# XIAO_ESP32S3_v1_1.net
KiCad netlist of a schematic drawn in EAGLE
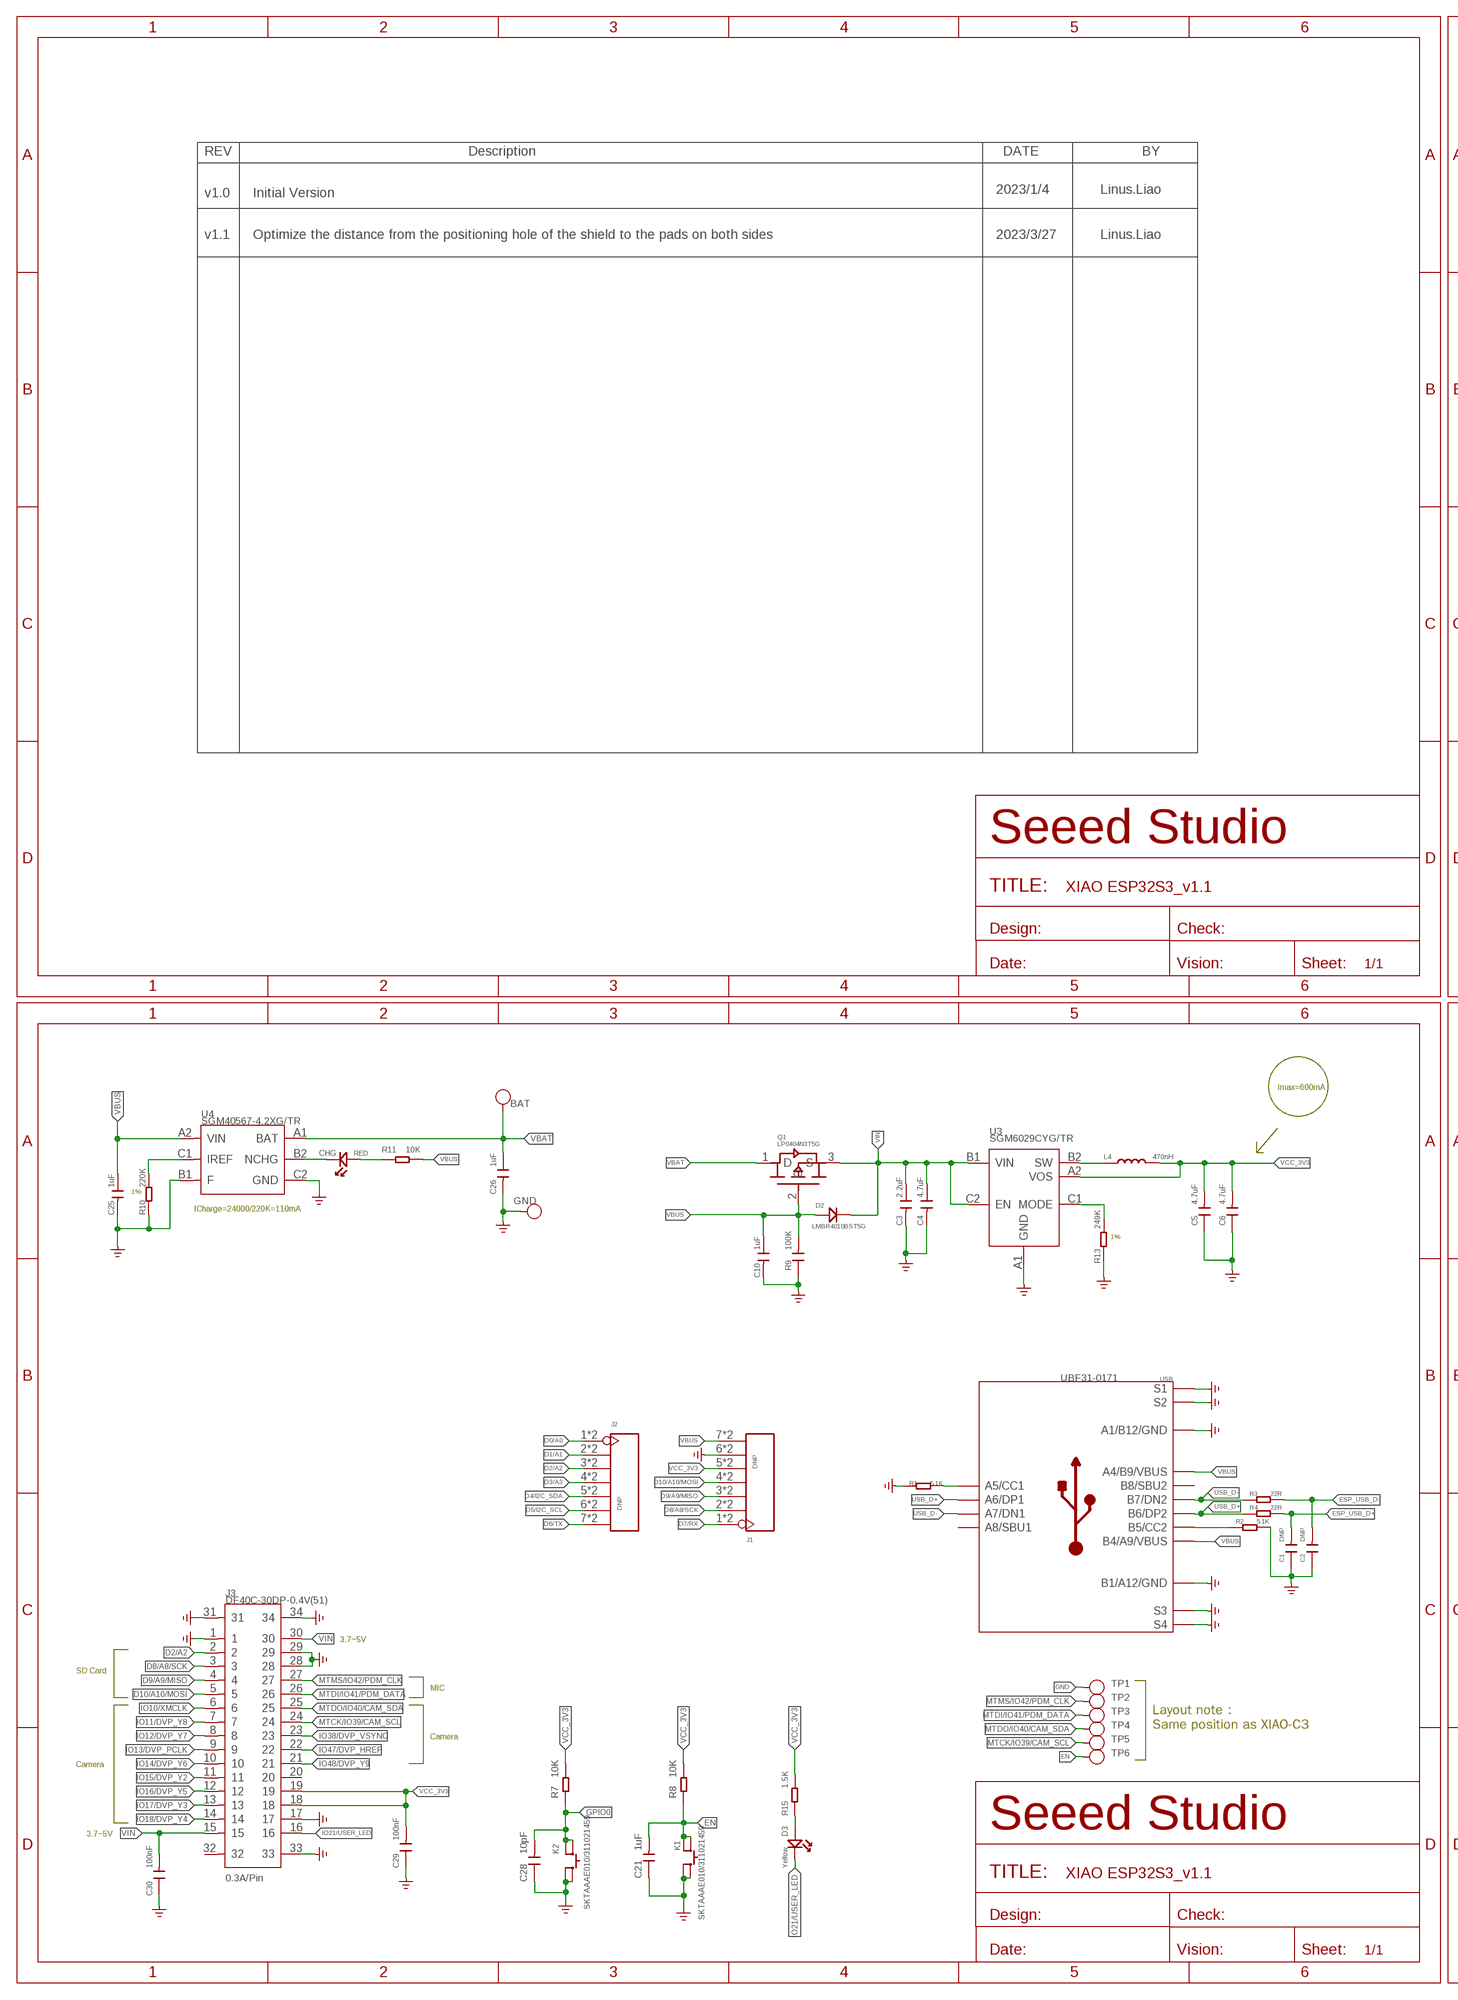
[diagram p0: schematic, sheet 1, part 1 of 2]
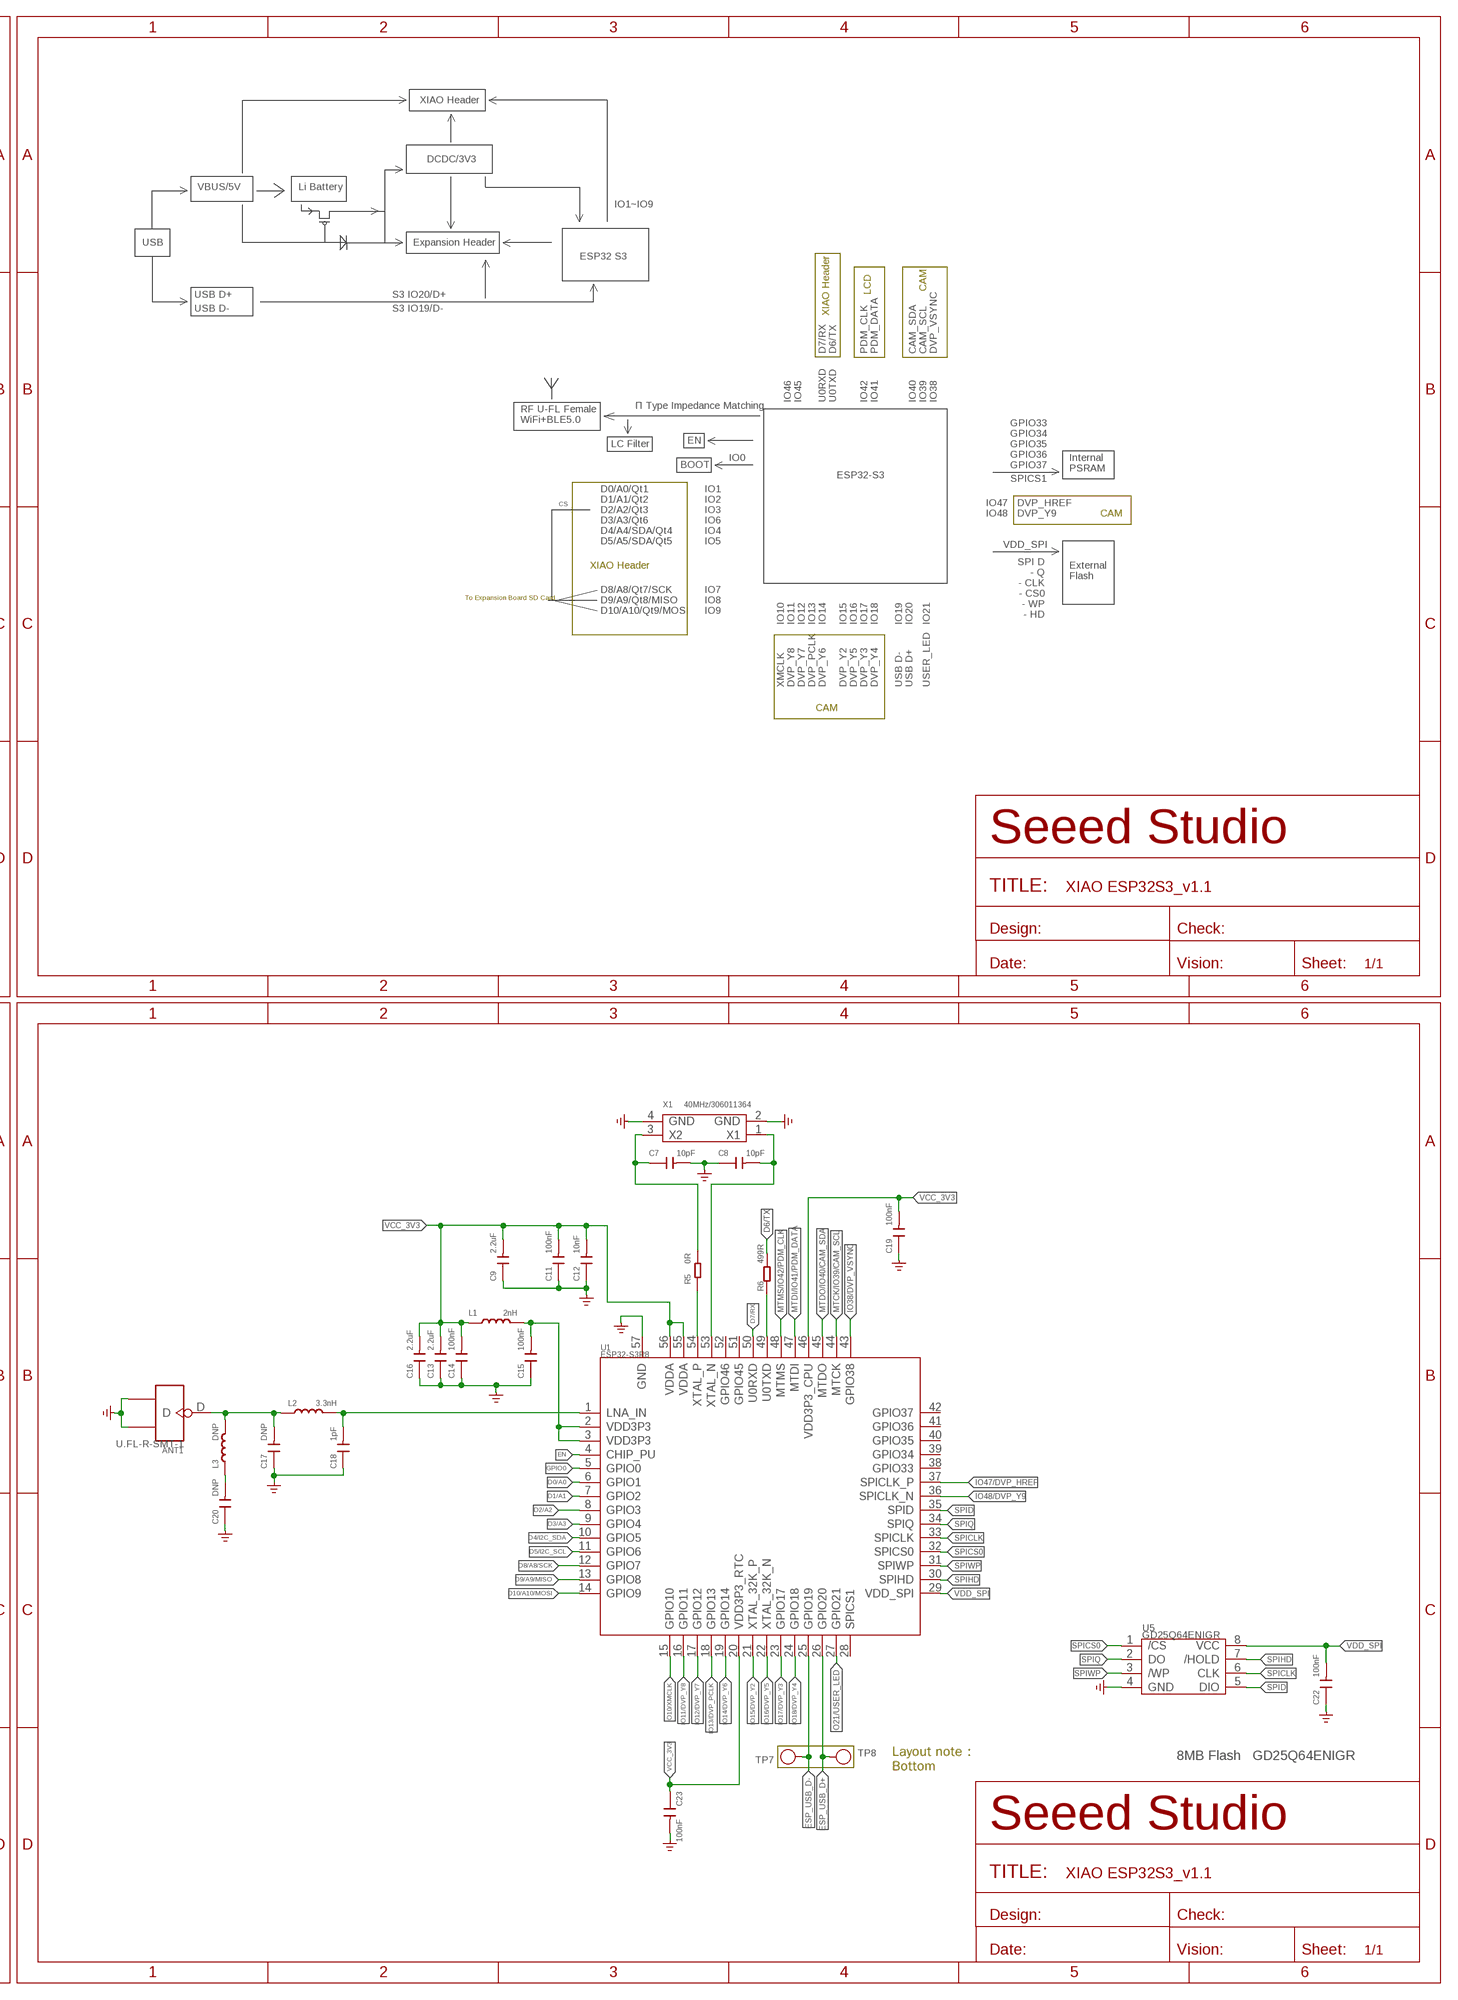
[diagram p1: schematic, sheet 1, part 2 of 2]

(export (version "E")
  (design (tool "Eeschema 10.0.6"))
  (components
    (comp (ref "ANT1")
      (value "U.FL-R-SMT-1")
      (footprint "eagle-import:U-FL3P-SMD-2.6X2.6X1.0MM")
      (libsource (lib "eagle-import") (part "ANTENNA-U-FL-320110048"))
    )
    (comp (ref "BAT")
      (value "VBAT")
      (footprint "eagle-import:TP-80X40MIL")
      (libsource (lib "eagle-import") (part "TEST-POINT'4080'"))
    )
    (comp (ref "C1")
      (value "DNP")
      (footprint "eagle-import:C0201")
      (libsource (lib "eagle-import") (part "CAP-0201"))
    )
    (comp (ref "C2")
      (value "DNP")
      (footprint "eagle-import:C0201")
      (libsource (lib "eagle-import") (part "CAP-0201"))
    )
    (comp (ref "C3")
      (value "2.2uF")
      (footprint "eagle-import:C0201")
      (libsource (lib "eagle-import") (part "CAP-0201"))
    )
    (comp (ref "C4")
      (value "4.7uF")
      (footprint "eagle-import:C0201")
      (libsource (lib "eagle-import") (part "CAP-0201"))
    )
    (comp (ref "C5")
      (value "4.7uF")
      (footprint "eagle-import:C0201")
      (libsource (lib "eagle-import") (part "CAP-0201"))
    )
    (comp (ref "C6")
      (value "4.7uF")
      (footprint "eagle-import:C0201")
      (libsource (lib "eagle-import") (part "CAP-0201"))
    )
    (comp (ref "C7")
      (value "10pF")
      (footprint "eagle-import:C0201")
      (libsource (lib "eagle-import") (part "CAP-0201"))
    )
    (comp (ref "C8")
      (value "10pF")
      (footprint "eagle-import:C0201")
      (libsource (lib "eagle-import") (part "CAP-0201"))
    )
    (comp (ref "C9")
      (value "2.2uF")
      (footprint "eagle-import:C0201")
      (libsource (lib "eagle-import") (part "CAP-0201"))
    )
    (comp (ref "C10")
      (value "1uF")
      (footprint "eagle-import:C0201")
      (libsource (lib "eagle-import") (part "CAP-0201"))
    )
    (comp (ref "C11")
      (value "100nF")
      (footprint "eagle-import:C0201")
      (libsource (lib "eagle-import") (part "CAP-0201"))
    )
    (comp (ref "C12")
      (value "10nF")
      (footprint "eagle-import:C0201")
      (libsource (lib "eagle-import") (part "CAP-0201"))
    )
    (comp (ref "C13")
      (value "2.2uF")
      (footprint "eagle-import:C0201")
      (libsource (lib "eagle-import") (part "CAP-0201"))
    )
    (comp (ref "C14")
      (value "100nF")
      (footprint "eagle-import:C0201")
      (libsource (lib "eagle-import") (part "CAP-0201"))
    )
    (comp (ref "C15")
      (value "100nF")
      (footprint "eagle-import:C0201")
      (libsource (lib "eagle-import") (part "CAP-0201"))
    )
    (comp (ref "C16")
      (value "2.2uF")
      (footprint "eagle-import:C0201")
      (libsource (lib "eagle-import") (part "CAP-0201"))
    )
    (comp (ref "C17")
      (value "DNP")
      (footprint "eagle-import:C0201")
      (libsource (lib "eagle-import") (part "CAP-0201"))
    )
    (comp (ref "C18")
      (value "1pF")
      (footprint "eagle-import:C0201")
      (libsource (lib "eagle-import") (part "CAP-0201"))
    )
    (comp (ref "C19")
      (value "100nF")
      (footprint "eagle-import:C0201")
      (libsource (lib "eagle-import") (part "CAP-0201"))
    )
    (comp (ref "C20")
      (value "DNP")
      (footprint "eagle-import:C0201")
      (libsource (lib "eagle-import") (part "CAP-0201"))
    )
    (comp (ref "C21")
      (value "1uF")
      (footprint "eagle-import:C0201")
      (libsource (lib "eagle-import") (part "CAP-0201"))
    )
    (comp (ref "C22")
      (value "100nF")
      (footprint "eagle-import:C0201")
      (libsource (lib "eagle-import") (part "CAP-0201"))
    )
    (comp (ref "C23")
      (value "100nF")
      (footprint "eagle-import:C0201")
      (libsource (lib "eagle-import") (part "CAP-0201"))
    )
    (comp (ref "C25")
      (value "1uF")
      (footprint "eagle-import:C0201")
      (libsource (lib "eagle-import") (part "CAP-0201"))
    )
    (comp (ref "C26")
      (value "1uF")
      (footprint "eagle-import:C0201")
      (libsource (lib "eagle-import") (part "CAP-0201"))
    )
    (comp (ref "C28")
      (value "10pF")
      (footprint "eagle-import:C0201")
      (libsource (lib "eagle-import") (part "CAP-0201"))
    )
    (comp (ref "C29")
      (value "100nF")
      (footprint "eagle-import:C0201")
      (libsource (lib "eagle-import") (part "CAP-0201"))
    )
    (comp (ref "C30")
      (value "100nF")
      (footprint "eagle-import:C0201")
      (libsource (lib "eagle-import") (part "CAP-0201"))
    )
    (comp (ref "CHG")
      (value "RED")
      (footprint "eagle-import:LED-0402")
      (libsource (lib "eagle-import") (part "LED-0402"))
    )
    (comp (ref "D2")
      (value "LMBR4010BST5G")
      (footprint "eagle-import:DFN1006-2L")
      (libsource (lib "eagle-import") (part "DIODEDFN1006(0402/SOD882)"))
    )
    (comp (ref "D3")
      (value "Yellow")
      (footprint "eagle-import:LED-0402")
      (libsource (lib "eagle-import") (part "LED-0402"))
    )
    (comp (ref "GND")
      (value "GND")
      (footprint "eagle-import:TP-80X40MIL")
      (libsource (lib "eagle-import") (part "TEST-POINT'4080'"))
    )
    (comp (ref "J1")
      (value "DNP")
      (footprint "eagle-import:H7-HALF-HOLE-2.54")
      (libsource (lib "eagle-import") (part "HEADER-7P-HALF-HOLE-2.54"))
    )
    (comp (ref "J2")
      (value "DNP")
      (footprint "eagle-import:H7-HALF-HOLE-2.54")
      (libsource (lib "eagle-import") (part "HEADER-7P-HALF-HOLE-2.54"))
    )
    (comp (ref "J3")
      (value "DF40C-30DP-0.4V(51)")
      (footprint "eagle-import:BTB30-0.4-7.52X2.97X1.14")
      (libsource (lib "eagle-import") (part "BTB-P4S30-HEAD"))
    )
    (comp (ref "K1")
      (value "SKTAAAE010/311021459")
      (footprint "eagle-import:SW4-SMD-2.8-2.6X1.6X0.53MM")
      (libsource (lib "eagle-import") (part "BUTTON-4P"))
    )
    (comp (ref "K2")
      (value "SKTAAAE010/311021459")
      (footprint "eagle-import:SW4-SMD-2.8-2.6X1.6X0.53MM")
      (libsource (lib "eagle-import") (part "BUTTON-4P"))
    )
    (comp (ref "L1")
      (value "2nH")
      (footprint "eagle-import:L0201")
      (libsource (lib "eagle-import") (part "INDUCTOR-0201"))
    )
    (comp (ref "L2")
      (value "3.3nH")
      (footprint "eagle-import:L0201")
      (libsource (lib "eagle-import") (part "INDUCTOR-0201"))
    )
    (comp (ref "L3")
      (value "DNP")
      (footprint "eagle-import:L0201")
      (libsource (lib "eagle-import") (part "INDUCTOR-0201"))
    )
    (comp (ref "L4")
      (value "470nH")
      (footprint "eagle-import:L0603")
      (libsource (lib "eagle-import") (part "L-0603"))
    )
    (comp (ref "Q1")
      (value "LP0404N3T5G")
      (footprint "eagle-import:PMOS_1.0_0.6_0.35MM")
      (libsource (lib "eagle-import") (part "PMOS_1.00.60.35MM"))
    )
    (comp (ref "R1")
      (value "5.1K")
      (footprint "eagle-import:R0201")
      (libsource (lib "eagle-import") (part "RES-0201"))
    )
    (comp (ref "R2")
      (value "5.1K")
      (footprint "eagle-import:R0201")
      (libsource (lib "eagle-import") (part "RES-0201"))
    )
    (comp (ref "R3")
      (value "22R")
      (footprint "eagle-import:R0201")
      (libsource (lib "eagle-import") (part "RES-0201"))
    )
    (comp (ref "R4")
      (value "22R")
      (footprint "eagle-import:R0201")
      (libsource (lib "eagle-import") (part "RES-0201"))
    )
    (comp (ref "R5")
      (value "0R")
      (footprint "eagle-import:R0201")
      (libsource (lib "eagle-import") (part "RES-0201"))
    )
    (comp (ref "R6")
      (value "499R")
      (footprint "eagle-import:R0201")
      (libsource (lib "eagle-import") (part "RES-0201"))
    )
    (comp (ref "R7")
      (value "10K")
      (footprint "eagle-import:R0201")
      (libsource (lib "eagle-import") (part "RES-0201"))
    )
    (comp (ref "R8")
      (value "10K")
      (footprint "eagle-import:R0201")
      (libsource (lib "eagle-import") (part "RES-0201"))
    )
    (comp (ref "R9")
      (value "100K")
      (footprint "eagle-import:C0201")
      (libsource (lib "eagle-import") (part "CAP-0201"))
    )
    (comp (ref "R10")
      (value "220K")
      (footprint "eagle-import:R0201")
      (libsource (lib "eagle-import") (part "RES-0201"))
    )
    (comp (ref "R11")
      (value "10K")
      (footprint "eagle-import:R0201")
      (libsource (lib "eagle-import") (part "RES-0201"))
    )
    (comp (ref "R13")
      (value "249K")
      (footprint "eagle-import:R0201")
      (libsource (lib "eagle-import") (part "RES-0201"))
    )
    (comp (ref "R15")
      (value "1.5K")
      (footprint "eagle-import:R0201")
      (libsource (lib "eagle-import") (part "RES-0201"))
    )
    (comp (ref "TP1")
      (value "TEST-POINT'4545'")
      (footprint "eagle-import:TP-D45MIL")
      (fields (field (name "PARTNO") "DNP"))
      (libsource (lib "eagle-import") (part "TEST-POINT'4545'"))
    )
    (comp (ref "TP2")
      (value "TEST-POINT'4545'")
      (footprint "eagle-import:TP-D45MIL")
      (fields (field (name "PARTNO") "DNP"))
      (libsource (lib "eagle-import") (part "TEST-POINT'4545'"))
    )
    (comp (ref "TP3")
      (value "TEST-POINT'4545'")
      (footprint "eagle-import:TP-D45MIL")
      (fields (field (name "PARTNO") "DNP"))
      (libsource (lib "eagle-import") (part "TEST-POINT'4545'"))
    )
    (comp (ref "TP4")
      (value "TEST-POINT'4545'")
      (footprint "eagle-import:TP-D45MIL")
      (fields (field (name "PARTNO") "DNP"))
      (libsource (lib "eagle-import") (part "TEST-POINT'4545'"))
    )
    (comp (ref "TP5")
      (value "TEST-POINT'4545'")
      (footprint "eagle-import:TP-D45MIL")
      (fields (field (name "PARTNO") "DNP"))
      (libsource (lib "eagle-import") (part "TEST-POINT'4545'"))
    )
    (comp (ref "TP6")
      (value "TEST-POINT'4545'")
      (footprint "eagle-import:TP-D45MIL")
      (fields (field (name "PARTNO") "DNP"))
      (libsource (lib "eagle-import") (part "TEST-POINT'4545'"))
    )
    (comp (ref "TP7")
      (value "TEST-POINT'4545'")
      (footprint "eagle-import:TP-D45MIL")
      (fields (field (name "PARTNO") "DNP"))
      (libsource (lib "eagle-import") (part "TEST-POINT'4545'"))
    )
    (comp (ref "TP8")
      (value "TEST-POINT'4545'")
      (footprint "eagle-import:TP-D45MIL")
      (fields (field (name "PARTNO") "DNP"))
      (libsource (lib "eagle-import") (part "TEST-POINT'4545'"))
    )
    (comp (ref "U1")
      (value "ESP32-S3R8")
      (footprint "eagle-import:QFN56G-0.4-7X7MM")
      (libsource (lib "eagle-import") (part "MCU-ESP32-S3"))
    )
    (comp (ref "U3")
      (value "SGM6029CYG/TR")
      (footprint "eagle-import:BGA6-0.35-0.745X10.95X0.4MM")
      (libsource (lib "eagle-import") (part "PMIC-SGM6029"))
    )
    (comp (ref "U4")
      (value "SGM40567-4.2XG/TR")
      (footprint "eagle-import:WLCSP-0.4-0.92X1.16X0.4MM")
      (libsource (lib "eagle-import") (part "PMIC-SGM40567"))
    )
    (comp (ref "U5")
      (value "GD25Q64ENIGR")
      (footprint "eagle-import:USON8-0.8-4X3MM")
      (libsource (lib "eagle-import") (part "FLASH-W25X80-FZBIHO"))
    )
    (comp (ref "USB")
      (value "UBF31-0171")
      (footprint "eagle-import:USB2.0-TYPE-C")
      (libsource (lib "eagle-import") (part "USB2.0-TYPE-C"))
    )
    (comp (ref "X1")
      (value "40MHz/306011364")
      (footprint "eagle-import:X4-SMD-1.6X1.2X0.35MM")
      (libsource (lib "eagle-import") (part "CRYSTAL-4P-1612"))
    )
  )
  (nets
    (net (code "1") (name "D0{slash}A0") (class "Default")
      (node (ref "J2") (pin "1") (pinfunction "1_1") (pintype "bidirectional"))
      (node (ref "J2") (pin "13") (pinfunction "1_13") (pintype "bidirectional"))
      (node (ref "U1") (pin "6") (pinfunction "GPIO1_6") (pintype "bidirectional"))
    )
    (net (code "2") (name "D1{slash}A1") (class "Default")
      (node (ref "J2") (pin "14") (pinfunction "2_14") (pintype "bidirectional"))
      (node (ref "J2") (pin "2") (pinfunction "2_2") (pintype "bidirectional"))
      (node (ref "U1") (pin "7") (pinfunction "GPIO2_7") (pintype "bidirectional"))
    )
    (net (code "3") (name "D2{slash}A2") (class "Default")
      (node (ref "J2") (pin "15") (pinfunction "3_15") (pintype "bidirectional"))
      (node (ref "J2") (pin "3") (pinfunction "3_3") (pintype "bidirectional"))
      (node (ref "J3") (pin "2") (pinfunction "2_2") (pintype "bidirectional"))
      (node (ref "U1") (pin "8") (pinfunction "GPIO3_8") (pintype "bidirectional"))
    )
    (net (code "4") (name "D3{slash}A3") (class "Default")
      (node (ref "J2") (pin "16") (pinfunction "4_16") (pintype "bidirectional"))
      (node (ref "J2") (pin "4") (pinfunction "4_4") (pintype "bidirectional"))
      (node (ref "U1") (pin "9") (pinfunction "GPIO4_9") (pintype "bidirectional"))
    )
    (net (code "5") (name "D4{slash}I2C_SDA") (class "Default")
      (node (ref "J2") (pin "17") (pinfunction "5_17") (pintype "bidirectional"))
      (node (ref "J2") (pin "5") (pinfunction "5_5") (pintype "bidirectional"))
      (node (ref "U1") (pin "10") (pinfunction "GPIO5_10") (pintype "bidirectional"))
    )
    (net (code "6") (name "D5{slash}I2C_SCL") (class "Default")
      (node (ref "J2") (pin "18") (pinfunction "6_18") (pintype "bidirectional"))
      (node (ref "J2") (pin "6") (pinfunction "6_6") (pintype "bidirectional"))
      (node (ref "U1") (pin "11") (pinfunction "GPIO6_11") (pintype "bidirectional"))
    )
    (net (code "7") (name "D6{slash}TX") (class "Default")
      (node (ref "J2") (pin "19") (pinfunction "7_19") (pintype "bidirectional"))
      (node (ref "J2") (pin "7") (pinfunction "7_7") (pintype "bidirectional"))
      (node (ref "R6") (pin "2") (pinfunction "2_2") (pintype "passive"))
    )
    (net (code "8") (name "D7{slash}RX") (class "Default")
      (node (ref "J1") (pin "1") (pinfunction "1_1") (pintype "bidirectional"))
      (node (ref "J1") (pin "13") (pinfunction "1_13") (pintype "bidirectional"))
      (node (ref "U1") (pin "50") (pinfunction "U0RXD_50") (pintype "bidirectional"))
    )
    (net (code "9") (name "D8{slash}A8{slash}SCK") (class "Default")
      (node (ref "J1") (pin "14") (pinfunction "2_14") (pintype "bidirectional"))
      (node (ref "J1") (pin "2") (pinfunction "2_2") (pintype "bidirectional"))
      (node (ref "J3") (pin "3") (pinfunction "3_3") (pintype "bidirectional"))
      (node (ref "U1") (pin "12") (pinfunction "GPIO7_12") (pintype "bidirectional"))
    )
    (net (code "10") (name "D9{slash}A9{slash}MISO") (class "Default")
      (node (ref "J1") (pin "15") (pinfunction "3_15") (pintype "bidirectional"))
      (node (ref "J1") (pin "3") (pinfunction "3_3") (pintype "bidirectional"))
      (node (ref "J3") (pin "4") (pinfunction "4_4") (pintype "bidirectional"))
      (node (ref "U1") (pin "13") (pinfunction "GPIO8_13") (pintype "bidirectional"))
    )
    (net (code "11") (name "D10{slash}A10{slash}MOSI") (class "Default")
      (node (ref "J1") (pin "16") (pinfunction "4_16") (pintype "bidirectional"))
      (node (ref "J1") (pin "4") (pinfunction "4_4") (pintype "bidirectional"))
      (node (ref "J3") (pin "5") (pinfunction "5_5") (pintype "bidirectional"))
      (node (ref "U1") (pin "14") (pinfunction "GPIO9_14") (pintype "bidirectional"))
    )
    (net (code "12") (name "EN") (class "Default")
      (node (ref "C21") (pin "2") (pinfunction "2_2") (pintype "passive"))
      (node (ref "K1") (pin "1") (pinfunction "A0_1") (pintype "bidirectional"))
      (node (ref "K1") (pin "3") (pinfunction "A1_3") (pintype "bidirectional"))
      (node (ref "R8") (pin "1") (pinfunction "1_1") (pintype "passive"))
      (node (ref "TP6") (pin "T") (pinfunction "T_T") (pintype "bidirectional"))
      (node (ref "U1") (pin "4") (pinfunction "CHIP_PU_4") (pintype "bidirectional"))
    )
    (net (code "13") (name "ESP_USB_D+") (class "Default")
      (node (ref "C1") (pin "2") (pinfunction "2_2") (pintype "passive"))
      (node (ref "R4") (pin "2") (pinfunction "2_2") (pintype "passive"))
      (node (ref "TP8") (pin "T") (pinfunction "T_T") (pintype "bidirectional"))
      (node (ref "U1") (pin "26") (pinfunction "GPIO20_26") (pintype "bidirectional"))
    )
    (net (code "14") (name "ESP_USB_D-") (class "Default")
      (node (ref "C2") (pin "2") (pinfunction "2_2") (pintype "passive"))
      (node (ref "R3") (pin "2") (pinfunction "2_2") (pintype "passive"))
      (node (ref "TP7") (pin "T") (pinfunction "T_T") (pintype "bidirectional"))
      (node (ref "U1") (pin "25") (pinfunction "GPIO19_25") (pintype "bidirectional"))
    )
    (net (code "15") (name "GND") (class "Default")
      (node (ref "ANT1") (pin "GND1") (pinfunction "GND1_GND1") (pintype "bidirectional"))
      (node (ref "ANT1") (pin "GND2") (pinfunction "GND2_GND2") (pintype "bidirectional"))
      (node (ref "C1") (pin "1") (pinfunction "1_1") (pintype "passive"))
      (node (ref "C10") (pin "2") (pinfunction "2_2") (pintype "passive"))
      (node (ref "C11") (pin "1") (pinfunction "1_1") (pintype "passive"))
      (node (ref "C12") (pin "1") (pinfunction "1_1") (pintype "passive"))
      (node (ref "C13") (pin "1") (pinfunction "1_1") (pintype "passive"))
      (node (ref "C14") (pin "1") (pinfunction "1_1") (pintype "passive"))
      (node (ref "C15") (pin "1") (pinfunction "1_1") (pintype "passive"))
      (node (ref "C16") (pin "1") (pinfunction "1_1") (pintype "passive"))
      (node (ref "C17") (pin "1") (pinfunction "1_1") (pintype "passive"))
      (node (ref "C18") (pin "1") (pinfunction "1_1") (pintype "passive"))
      (node (ref "C19") (pin "1") (pinfunction "1_1") (pintype "passive"))
      (node (ref "C2") (pin "1") (pinfunction "1_1") (pintype "passive"))
      (node (ref "C20") (pin "1") (pinfunction "1_1") (pintype "passive"))
      (node (ref "C21") (pin "1") (pinfunction "1_1") (pintype "passive"))
      (node (ref "C22") (pin "1") (pinfunction "1_1") (pintype "passive"))
      (node (ref "C23") (pin "2") (pinfunction "2_2") (pintype "passive"))
      (node (ref "C25") (pin "2") (pinfunction "2_2") (pintype "passive"))
      (node (ref "C26") (pin "2") (pinfunction "2_2") (pintype "passive"))
      (node (ref "C28") (pin "1") (pinfunction "1_1") (pintype "passive"))
      (node (ref "C29") (pin "1") (pinfunction "1_1") (pintype "passive"))
      (node (ref "C3") (pin "2") (pinfunction "2_2") (pintype "passive"))
      (node (ref "C30") (pin "1") (pinfunction "1_1") (pintype "passive"))
      (node (ref "C4") (pin "2") (pinfunction "2_2") (pintype "passive"))
      (node (ref "C5") (pin "1") (pinfunction "1_1") (pintype "passive"))
      (node (ref "C6") (pin "1") (pinfunction "1_1") (pintype "passive"))
      (node (ref "C7") (pin "2") (pinfunction "2_2") (pintype "passive"))
      (node (ref "C8") (pin "1") (pinfunction "1_1") (pintype "passive"))
      (node (ref "C9") (pin "1") (pinfunction "1_1") (pintype "passive"))
      (node (ref "GND") (pin "1") (pinfunction "T_1") (pintype "bidirectional"))
      (node (ref "J1") (pin "18") (pinfunction "6_18") (pintype "bidirectional"))
      (node (ref "J1") (pin "6") (pinfunction "6_6") (pintype "bidirectional"))
      (node (ref "J3") (pin "1") (pinfunction "1_1") (pintype "bidirectional"))
      (node (ref "J3") (pin "17") (pinfunction "17_17") (pintype "bidirectional"))
      (node (ref "J3") (pin "28") (pinfunction "28_28") (pintype "bidirectional"))
      (node (ref "J3") (pin "29") (pinfunction "29_29") (pintype "bidirectional"))
      (node (ref "J3") (pin "31") (pinfunction "31_31") (pintype "bidirectional"))
      (node (ref "J3") (pin "33") (pinfunction "33_33") (pintype "bidirectional"))
      (node (ref "J3") (pin "34") (pinfunction "34_34") (pintype "bidirectional"))
      (node (ref "K1") (pin "2") (pinfunction "B0_2") (pintype "bidirectional"))
      (node (ref "K1") (pin "4") (pinfunction "B1_4") (pintype "bidirectional"))
      (node (ref "K2") (pin "2") (pinfunction "B0_2") (pintype "bidirectional"))
      (node (ref "K2") (pin "4") (pinfunction "B1_4") (pintype "bidirectional"))
      (node (ref "R1") (pin "1") (pinfunction "1_1") (pintype "passive"))
      (node (ref "R10") (pin "1") (pinfunction "1_1") (pintype "passive"))
      (node (ref "R13") (pin "1") (pinfunction "1_1") (pintype "passive"))
      (node (ref "R2") (pin "2") (pinfunction "2_2") (pintype "passive"))
      (node (ref "R9") (pin "1") (pinfunction "1_1") (pintype "passive"))
      (node (ref "TP1") (pin "T") (pinfunction "T_T") (pintype "bidirectional"))
      (node (ref "U1") (pin "57") (pinfunction "GND_57") (pintype "bidirectional"))
      (node (ref "U3") (pin "A1") (pinfunction "GND_A1") (pintype "bidirectional"))
      (node (ref "U4") (pin "B1") (pinfunction "F_B1") (pintype "bidirectional"))
      (node (ref "U4") (pin "C2") (pinfunction "GND_C2") (pintype "bidirectional"))
      (node (ref "U5") (pin "4") (pinfunction "GND_4") (pintype "bidirectional"))
      (node (ref "USB") (pin "A1_B12") (pinfunction "A1/B12/GND_A1_B12") (pintype "bidirectional"))
      (node (ref "USB") (pin "B1_A12") (pinfunction "B1/A12/GND_B1_A12") (pintype "bidirectional"))
      (node (ref "USB") (pin "S1") (pinfunction "S1_S1") (pintype "bidirectional"))
      (node (ref "USB") (pin "S2") (pinfunction "S2_S2") (pintype "bidirectional"))
      (node (ref "USB") (pin "S3") (pinfunction "S3_S3") (pintype "bidirectional"))
      (node (ref "USB") (pin "S4") (pinfunction "S4_S4") (pintype "bidirectional"))
      (node (ref "USB") (pin "S5") (pinfunction "S1_S5") (pintype "bidirectional"))
      (node (ref "USB") (pin "S6") (pinfunction "S2_S6") (pintype "bidirectional"))
      (node (ref "X1") (pin "2") (pinfunction "GND_2") (pintype "bidirectional"))
      (node (ref "X1") (pin "4") (pinfunction "GND_4") (pintype "bidirectional"))
    )
    (net (code "16") (name "GPIO0") (class "Default")
      (node (ref "C28") (pin "2") (pinfunction "2_2") (pintype "passive"))
      (node (ref "K2") (pin "1") (pinfunction "A0_1") (pintype "bidirectional"))
      (node (ref "K2") (pin "3") (pinfunction "A1_3") (pintype "bidirectional"))
      (node (ref "R7") (pin "1") (pinfunction "1_1") (pintype "passive"))
      (node (ref "U1") (pin "5") (pinfunction "GPIO0_5") (pintype "bidirectional"))
    )
    (net (code "17") (name "IO10{slash}XMCLK") (class "Default")
      (node (ref "J3") (pin "6") (pinfunction "6_6") (pintype "bidirectional"))
      (node (ref "U1") (pin "15") (pinfunction "GPIO10_15") (pintype "bidirectional"))
    )
    (net (code "18") (name "IO11{slash}DVP_Y8") (class "Default")
      (node (ref "J3") (pin "7") (pinfunction "7_7") (pintype "bidirectional"))
      (node (ref "U1") (pin "16") (pinfunction "GPIO11_16") (pintype "bidirectional"))
    )
    (net (code "19") (name "IO12{slash}DVP_Y7") (class "Default")
      (node (ref "J3") (pin "8") (pinfunction "8_8") (pintype "bidirectional"))
      (node (ref "U1") (pin "17") (pinfunction "GPIO12_17") (pintype "bidirectional"))
    )
    (net (code "20") (name "IO13{slash}DVP_PCLK") (class "Default")
      (node (ref "J3") (pin "9") (pinfunction "9_9") (pintype "bidirectional"))
      (node (ref "U1") (pin "18") (pinfunction "GPIO13_18") (pintype "bidirectional"))
    )
    (net (code "21") (name "IO14{slash}DVP_Y6") (class "Default")
      (node (ref "J3") (pin "10") (pinfunction "10_10") (pintype "bidirectional"))
      (node (ref "U1") (pin "19") (pinfunction "GPIO14_19") (pintype "bidirectional"))
    )
    (net (code "22") (name "IO15{slash}DVP_Y2") (class "Default")
      (node (ref "J3") (pin "11") (pinfunction "11_11") (pintype "bidirectional"))
      (node (ref "U1") (pin "21") (pinfunction "XTAL_32K_P_21") (pintype "bidirectional"))
    )
    (net (code "23") (name "IO16{slash}DVP_Y5") (class "Default")
      (node (ref "J3") (pin "12") (pinfunction "12_12") (pintype "bidirectional"))
      (node (ref "U1") (pin "22") (pinfunction "XTAL_32K_N_22") (pintype "bidirectional"))
    )
    (net (code "24") (name "IO17{slash}DVP_Y3") (class "Default")
      (node (ref "J3") (pin "13") (pinfunction "13_13") (pintype "bidirectional"))
      (node (ref "U1") (pin "23") (pinfunction "GPIO17_23") (pintype "bidirectional"))
    )
    (net (code "25") (name "IO18{slash}DVP_Y4") (class "Default")
      (node (ref "J3") (pin "14") (pinfunction "14_14") (pintype "bidirectional"))
      (node (ref "U1") (pin "24") (pinfunction "GPIO18_24") (pintype "bidirectional"))
    )
    (net (code "26") (name "IO21{slash}USER_LED") (class "Default")
      (node (ref "D3") (pin "-") (pinfunction "-_-") (pintype "passive"))
      (node (ref "J3") (pin "16") (pinfunction "16_16") (pintype "bidirectional"))
      (node (ref "U1") (pin "27") (pinfunction "GPIO21_27") (pintype "bidirectional"))
    )
    (net (code "27") (name "IO38{slash}DVP_VSYNC") (class "Default")
      (node (ref "J3") (pin "23") (pinfunction "23_23") (pintype "bidirectional"))
      (node (ref "U1") (pin "43") (pinfunction "GPIO38_43") (pintype "bidirectional"))
    )
    (net (code "28") (name "IO47{slash}DVP_HREF") (class "Default")
      (node (ref "J3") (pin "22") (pinfunction "22_22") (pintype "bidirectional"))
      (node (ref "U1") (pin "37") (pinfunction "SPICLK_P_37") (pintype "bidirectional"))
    )
    (net (code "29") (name "IO48{slash}DVP_Y9") (class "Default")
      (node (ref "J3") (pin "21") (pinfunction "21_21") (pintype "bidirectional"))
      (node (ref "U1") (pin "36") (pinfunction "SPICLK_N_36") (pintype "bidirectional"))
    )
    (net (code "30") (name "MTCK{slash}IO39{slash}CAM_SCL") (class "Default")
      (node (ref "J3") (pin "24") (pinfunction "24_24") (pintype "bidirectional"))
      (node (ref "TP5") (pin "T") (pinfunction "T_T") (pintype "bidirectional"))
      (node (ref "U1") (pin "44") (pinfunction "MTCK_44") (pintype "bidirectional"))
    )
    (net (code "31") (name "MTDI{slash}IO41{slash}PDM_DATA") (class "Default")
      (node (ref "J3") (pin "26") (pinfunction "26_26") (pintype "bidirectional"))
      (node (ref "TP3") (pin "T") (pinfunction "T_T") (pintype "bidirectional"))
      (node (ref "U1") (pin "47") (pinfunction "MTDI_47") (pintype "bidirectional"))
    )
    (net (code "32") (name "MTDO{slash}IO40{slash}CAM_SDA") (class "Default")
      (node (ref "J3") (pin "25") (pinfunction "25_25") (pintype "bidirectional"))
      (node (ref "TP4") (pin "T") (pinfunction "T_T") (pintype "bidirectional"))
      (node (ref "U1") (pin "45") (pinfunction "MTDO_45") (pintype "bidirectional"))
    )
    (net (code "33") (name "MTMS{slash}IO42{slash}PDM_CLK") (class "Default")
      (node (ref "J3") (pin "27") (pinfunction "27_27") (pintype "bidirectional"))
      (node (ref "TP2") (pin "T") (pinfunction "T_T") (pintype "bidirectional"))
      (node (ref "U1") (pin "48") (pinfunction "MTMS_48") (pintype "bidirectional"))
    )
    (net (code "34") (name "Net-(ANT1-PadD)") (class "Default")
      (node (ref "ANT1") (pin "D") (pinfunction "D_D") (pintype "bidirectional"))
      (node (ref "C17") (pin "2") (pinfunction "2_2") (pintype "passive"))
      (node (ref "L2") (pin "1") (pinfunction "1_1") (pintype "passive"))
      (node (ref "L3") (pin "2") (pinfunction "2_2") (pintype "passive"))
    )
    (net (code "35") (name "Net-(C15-Pad2)") (class "Default")
      (node (ref "C15") (pin "2") (pinfunction "2_2") (pintype "passive"))
      (node (ref "L1") (pin "2") (pinfunction "2_2") (pintype "passive"))
      (node (ref "U1") (pin "2") (pinfunction "VDD3P3_2") (pintype "bidirectional"))
      (node (ref "U1") (pin "3") (pinfunction "VDD3P3_3") (pintype "bidirectional"))
    )
    (net (code "36") (name "Net-(C20-Pad2)") (class "Default")
      (node (ref "C20") (pin "2") (pinfunction "2_2") (pintype "passive"))
      (node (ref "L3") (pin "1") (pinfunction "1_1") (pintype "passive"))
    )
    (net (code "37") (name "Net-(CHG-Pad+)") (class "Default")
      (node (ref "CHG") (pin "+") (pinfunction "+_+") (pintype "passive"))
      (node (ref "R11") (pin "2") (pinfunction "2_2") (pintype "passive"))
    )
    (net (code "38") (name "Net-(D3-Pad+)") (class "Default")
      (node (ref "D3") (pin "+") (pinfunction "+_+") (pintype "passive"))
      (node (ref "R15") (pin "1") (pinfunction "1_1") (pintype "passive"))
    )
    (net (code "39") (name "Net-(U1-LNA_IN)") (class "Default")
      (node (ref "C18") (pin "2") (pinfunction "2_2") (pintype "passive"))
      (node (ref "L2") (pin "2") (pinfunction "2_2") (pintype "passive"))
      (node (ref "U1") (pin "1") (pinfunction "LNA_IN_1") (pintype "bidirectional"))
    )
    (net (code "40") (name "Net-(U1-U0TXD)") (class "Default")
      (node (ref "R6") (pin "1") (pinfunction "1_1") (pintype "passive"))
      (node (ref "U1") (pin "49") (pinfunction "U0TXD_49") (pintype "bidirectional"))
    )
    (net (code "41") (name "Net-(U1-XTAL_N)") (class "Default")
      (node (ref "C8") (pin "2") (pinfunction "2_2") (pintype "passive"))
      (node (ref "U1") (pin "53") (pinfunction "XTAL_N_53") (pintype "bidirectional"))
      (node (ref "X1") (pin "1") (pinfunction "X1_1") (pintype "bidirectional"))
    )
    (net (code "42") (name "Net-(U1-XTAL_P)") (class "Default")
      (node (ref "R5") (pin "1") (pinfunction "1_1") (pintype "passive"))
      (node (ref "U1") (pin "54") (pinfunction "XTAL_P_54") (pintype "bidirectional"))
    )
    (net (code "43") (name "Net-(U3-MODE)") (class "Default")
      (node (ref "R13") (pin "2") (pinfunction "2_2") (pintype "passive"))
      (node (ref "U3") (pin "C1") (pinfunction "MODE_C1") (pintype "bidirectional"))
    )
    (net (code "44") (name "Net-(U3-SW)") (class "Default")
      (node (ref "L4") (pin "1") (pinfunction "1_1") (pintype "passive"))
      (node (ref "U3") (pin "B2") (pinfunction "SW_B2") (pintype "bidirectional"))
    )
    (net (code "45") (name "Net-(U4-IREF)") (class "Default")
      (node (ref "R10") (pin "2") (pinfunction "2_2") (pintype "passive"))
      (node (ref "U4") (pin "C1") (pinfunction "IREF_C1") (pintype "bidirectional"))
    )
    (net (code "46") (name "Net-(U4-NCHG)") (class "Default")
      (node (ref "CHG") (pin "-") (pinfunction "-_-") (pintype "passive"))
      (node (ref "U4") (pin "B2") (pinfunction "NCHG_B2") (pintype "bidirectional"))
    )
    (net (code "47") (name "Net-(USB-A5{slash}CC1)") (class "Default")
      (node (ref "R1") (pin "2") (pinfunction "2_2") (pintype "passive"))
      (node (ref "USB") (pin "A5") (pinfunction "A5/CC1_A5") (pintype "bidirectional"))
    )
    (net (code "48") (name "Net-(USB-B5{slash}CC2)") (class "Default")
      (node (ref "R2") (pin "1") (pinfunction "1_1") (pintype "passive"))
      (node (ref "USB") (pin "B5") (pinfunction "B5/CC2_B5") (pintype "bidirectional"))
    )
    (net (code "49") (name "Net-(X1-X2)") (class "Default")
      (node (ref "C7") (pin "1") (pinfunction "1_1") (pintype "passive"))
      (node (ref "R5") (pin "2") (pinfunction "2_2") (pintype "passive"))
      (node (ref "X1") (pin "3") (pinfunction "X2_3") (pintype "bidirectional"))
    )
    (net (code "50") (name "SPICLK") (class "Default")
      (node (ref "U1") (pin "33") (pinfunction "SPICLK_33") (pintype "bidirectional"))
      (node (ref "U5") (pin "6") (pinfunction "CLK_6") (pintype "bidirectional"))
    )
    (net (code "51") (name "SPICS0") (class "Default")
      (node (ref "U1") (pin "32") (pinfunction "SPICS0_32") (pintype "bidirectional"))
      (node (ref "U5") (pin "1") (pinfunction "/CS_1") (pintype "bidirectional"))
    )
    (net (code "52") (name "SPID") (class "Default")
      (node (ref "U1") (pin "35") (pinfunction "SPID_35") (pintype "bidirectional"))
      (node (ref "U5") (pin "5") (pinfunction "DIO_5") (pintype "bidirectional"))
    )
    (net (code "53") (name "SPIHD") (class "Default")
      (node (ref "U1") (pin "30") (pinfunction "SPIHD_30") (pintype "bidirectional"))
      (node (ref "U5") (pin "7") (pinfunction "/HOLD_7") (pintype "bidirectional"))
    )
    (net (code "54") (name "SPIQ") (class "Default")
      (node (ref "U1") (pin "34") (pinfunction "SPIQ_34") (pintype "bidirectional"))
      (node (ref "U5") (pin "2") (pinfunction "DO_2") (pintype "bidirectional"))
    )
    (net (code "55") (name "SPIWP") (class "Default")
      (node (ref "U1") (pin "31") (pinfunction "SPIWP_31") (pintype "bidirectional"))
      (node (ref "U5") (pin "3") (pinfunction "/WP_3") (pintype "bidirectional"))
    )
    (net (code "56") (name "USB_D+") (class "Default")
      (node (ref "R4") (pin "1") (pinfunction "1_1") (pintype "passive"))
      (node (ref "USB") (pin "A6") (pinfunction "A6/DP1_A6") (pintype "bidirectional"))
      (node (ref "USB") (pin "B6") (pinfunction "B6/DP2_B6") (pintype "bidirectional"))
    )
    (net (code "57") (name "USB_D-") (class "Default")
      (node (ref "R3") (pin "1") (pinfunction "1_1") (pintype "passive"))
      (node (ref "USB") (pin "A7") (pinfunction "A7/DN1_A7") (pintype "bidirectional"))
      (node (ref "USB") (pin "B7") (pinfunction "B7/DN2_B7") (pintype "bidirectional"))
    )
    (net (code "58") (name "VBAT") (class "Default")
      (node (ref "BAT") (pin "1") (pinfunction "T_1") (pintype "bidirectional"))
      (node (ref "C26") (pin "1") (pinfunction "1_1") (pintype "passive"))
      (node (ref "Q1") (pin "1") (pinfunction "D_1") (pintype "bidirectional"))
      (node (ref "U4") (pin "A1") (pinfunction "BAT_A1") (pintype "bidirectional"))
    )
    (net (code "59") (name "VBUS") (class "Default")
      (node (ref "C10") (pin "1") (pinfunction "1_1") (pintype "passive"))
      (node (ref "C25") (pin "1") (pinfunction "1_1") (pintype "passive"))
      (node (ref "D2") (pin "+") (pinfunction "+_+") (pintype "passive"))
      (node (ref "J1") (pin "19") (pinfunction "7_19") (pintype "bidirectional"))
      (node (ref "J1") (pin "7") (pinfunction "7_7") (pintype "bidirectional"))
      (node (ref "Q1") (pin "2") (pinfunction "G_2") (pintype "bidirectional"))
      (node (ref "R11") (pin "1") (pinfunction "1_1") (pintype "passive"))
      (node (ref "R9") (pin "2") (pinfunction "2_2") (pintype "passive"))
      (node (ref "U4") (pin "A2") (pinfunction "VIN_A2") (pintype "bidirectional"))
      (node (ref "USB") (pin "A4_B9") (pinfunction "A4/B9/VBUS_A4_B9") (pintype "bidirectional"))
      (node (ref "USB") (pin "B4_A9") (pinfunction "B4/A9/VBUS_B4_A9") (pintype "bidirectional"))
    )
    (net (code "60") (name "VCC_3V3") (class "Default")
      (node (ref "C11") (pin "2") (pinfunction "2_2") (pintype "passive"))
      (node (ref "C12") (pin "2") (pinfunction "2_2") (pintype "passive"))
      (node (ref "C13") (pin "2") (pinfunction "2_2") (pintype "passive"))
      (node (ref "C14") (pin "2") (pinfunction "2_2") (pintype "passive"))
      (node (ref "C16") (pin "2") (pinfunction "2_2") (pintype "passive"))
      (node (ref "C19") (pin "2") (pinfunction "2_2") (pintype "passive"))
      (node (ref "C23") (pin "1") (pinfunction "1_1") (pintype "passive"))
      (node (ref "C29") (pin "2") (pinfunction "2_2") (pintype "passive"))
      (node (ref "C5") (pin "2") (pinfunction "2_2") (pintype "passive"))
      (node (ref "C6") (pin "2") (pinfunction "2_2") (pintype "passive"))
      (node (ref "C9") (pin "2") (pinfunction "2_2") (pintype "passive"))
      (node (ref "J1") (pin "17") (pinfunction "5_17") (pintype "bidirectional"))
      (node (ref "J1") (pin "5") (pinfunction "5_5") (pintype "bidirectional"))
      (node (ref "J3") (pin "18") (pinfunction "18_18") (pintype "bidirectional"))
      (node (ref "J3") (pin "19") (pinfunction "19_19") (pintype "bidirectional"))
      (node (ref "L1") (pin "1") (pinfunction "1_1") (pintype "passive"))
      (node (ref "L4") (pin "2") (pinfunction "2_2") (pintype "passive"))
      (node (ref "R15") (pin "2") (pinfunction "2_2") (pintype "passive"))
      (node (ref "R7") (pin "2") (pinfunction "2_2") (pintype "passive"))
      (node (ref "R8") (pin "2") (pinfunction "2_2") (pintype "passive"))
      (node (ref "U1") (pin "20") (pinfunction "VDD3P3_RTC_20") (pintype "bidirectional"))
      (node (ref "U1") (pin "46") (pinfunction "VDD3P3_CPU_46") (pintype "bidirectional"))
      (node (ref "U1") (pin "55") (pinfunction "VDDA_55") (pintype "bidirectional"))
      (node (ref "U1") (pin "56") (pinfunction "VDDA_56") (pintype "bidirectional"))
      (node (ref "U3") (pin "A2") (pinfunction "VOS_A2") (pintype "bidirectional"))
    )
    (net (code "61") (name "VDD_SPI") (class "Default")
      (node (ref "C22") (pin "2") (pinfunction "2_2") (pintype "passive"))
      (node (ref "U1") (pin "29") (pinfunction "VDD_SPI_29") (pintype "bidirectional"))
      (node (ref "U5") (pin "8") (pinfunction "VCC_8") (pintype "bidirectional"))
    )
    (net (code "62") (name "VIN") (class "Default")
      (node (ref "C3") (pin "1") (pinfunction "1_1") (pintype "passive"))
      (node (ref "C30") (pin "2") (pinfunction "2_2") (pintype "passive"))
      (node (ref "C4") (pin "1") (pinfunction "1_1") (pintype "passive"))
      (node (ref "D2") (pin "-") (pinfunction "-_-") (pintype "passive"))
      (node (ref "J3") (pin "15") (pinfunction "15_15") (pintype "bidirectional"))
      (node (ref "J3") (pin "30") (pinfunction "30_30") (pintype "bidirectional"))
      (node (ref "Q1") (pin "3") (pinfunction "S_3") (pintype "bidirectional"))
      (node (ref "U3") (pin "B1") (pinfunction "VIN_B1") (pintype "bidirectional"))
      (node (ref "U3") (pin "C2") (pinfunction "EN_C2") (pintype "bidirectional"))
    )
    (net (code "63") (name "unconnected-(J3-Pad20)") (class "Default")
      (node (ref "J3") (pin "20") (pinfunction "20_20") (pintype "bidirectional"))
    )
    (net (code "64") (name "unconnected-(J3-Pad32)") (class "Default")
      (node (ref "J3") (pin "32") (pinfunction "32_32") (pintype "bidirectional"))
    )
    (net (code "65") (name "unconnected-(U1-GPIO33-Pad38)") (class "Default")
      (node (ref "U1") (pin "38") (pinfunction "GPIO33_38") (pintype "bidirectional"))
    )
    (net (code "66") (name "unconnected-(U1-GPIO34-Pad39)") (class "Default")
      (node (ref "U1") (pin "39") (pinfunction "GPIO34_39") (pintype "bidirectional"))
    )
    (net (code "67") (name "unconnected-(U1-GPIO35-Pad40)") (class "Default")
      (node (ref "U1") (pin "40") (pinfunction "GPIO35_40") (pintype "bidirectional"))
    )
    (net (code "68") (name "unconnected-(U1-GPIO36-Pad41)") (class "Default")
      (node (ref "U1") (pin "41") (pinfunction "GPIO36_41") (pintype "bidirectional"))
    )
    (net (code "69") (name "unconnected-(U1-GPIO37-Pad42)") (class "Default")
      (node (ref "U1") (pin "42") (pinfunction "GPIO37_42") (pintype "bidirectional"))
    )
    (net (code "70") (name "unconnected-(U1-GPIO45-Pad51)") (class "Default")
      (node (ref "U1") (pin "51") (pinfunction "GPIO45_51") (pintype "bidirectional"))
    )
    (net (code "71") (name "unconnected-(U1-GPIO46-Pad52)") (class "Default")
      (node (ref "U1") (pin "52") (pinfunction "GPIO46_52") (pintype "bidirectional"))
    )
    (net (code "72") (name "unconnected-(U1-SPICS1-Pad28)") (class "Default")
      (node (ref "U1") (pin "28") (pinfunction "SPICS1_28") (pintype "bidirectional"))
    )
    (net (code "73") (name "unconnected-(USB-A8{slash}SBU1-PadA8)") (class "Default")
      (node (ref "USB") (pin "A8") (pinfunction "A8/SBU1_A8") (pintype "bidirectional"))
    )
    (net (code "74") (name "unconnected-(USB-B8{slash}SBU2-PadB8)") (class "Default")
      (node (ref "USB") (pin "B8") (pinfunction "B8/SBU2_B8") (pintype "bidirectional"))
    )
  )
)
